# step_up_converter.net
KiCad netlist of a schematic drawn in EAGLE
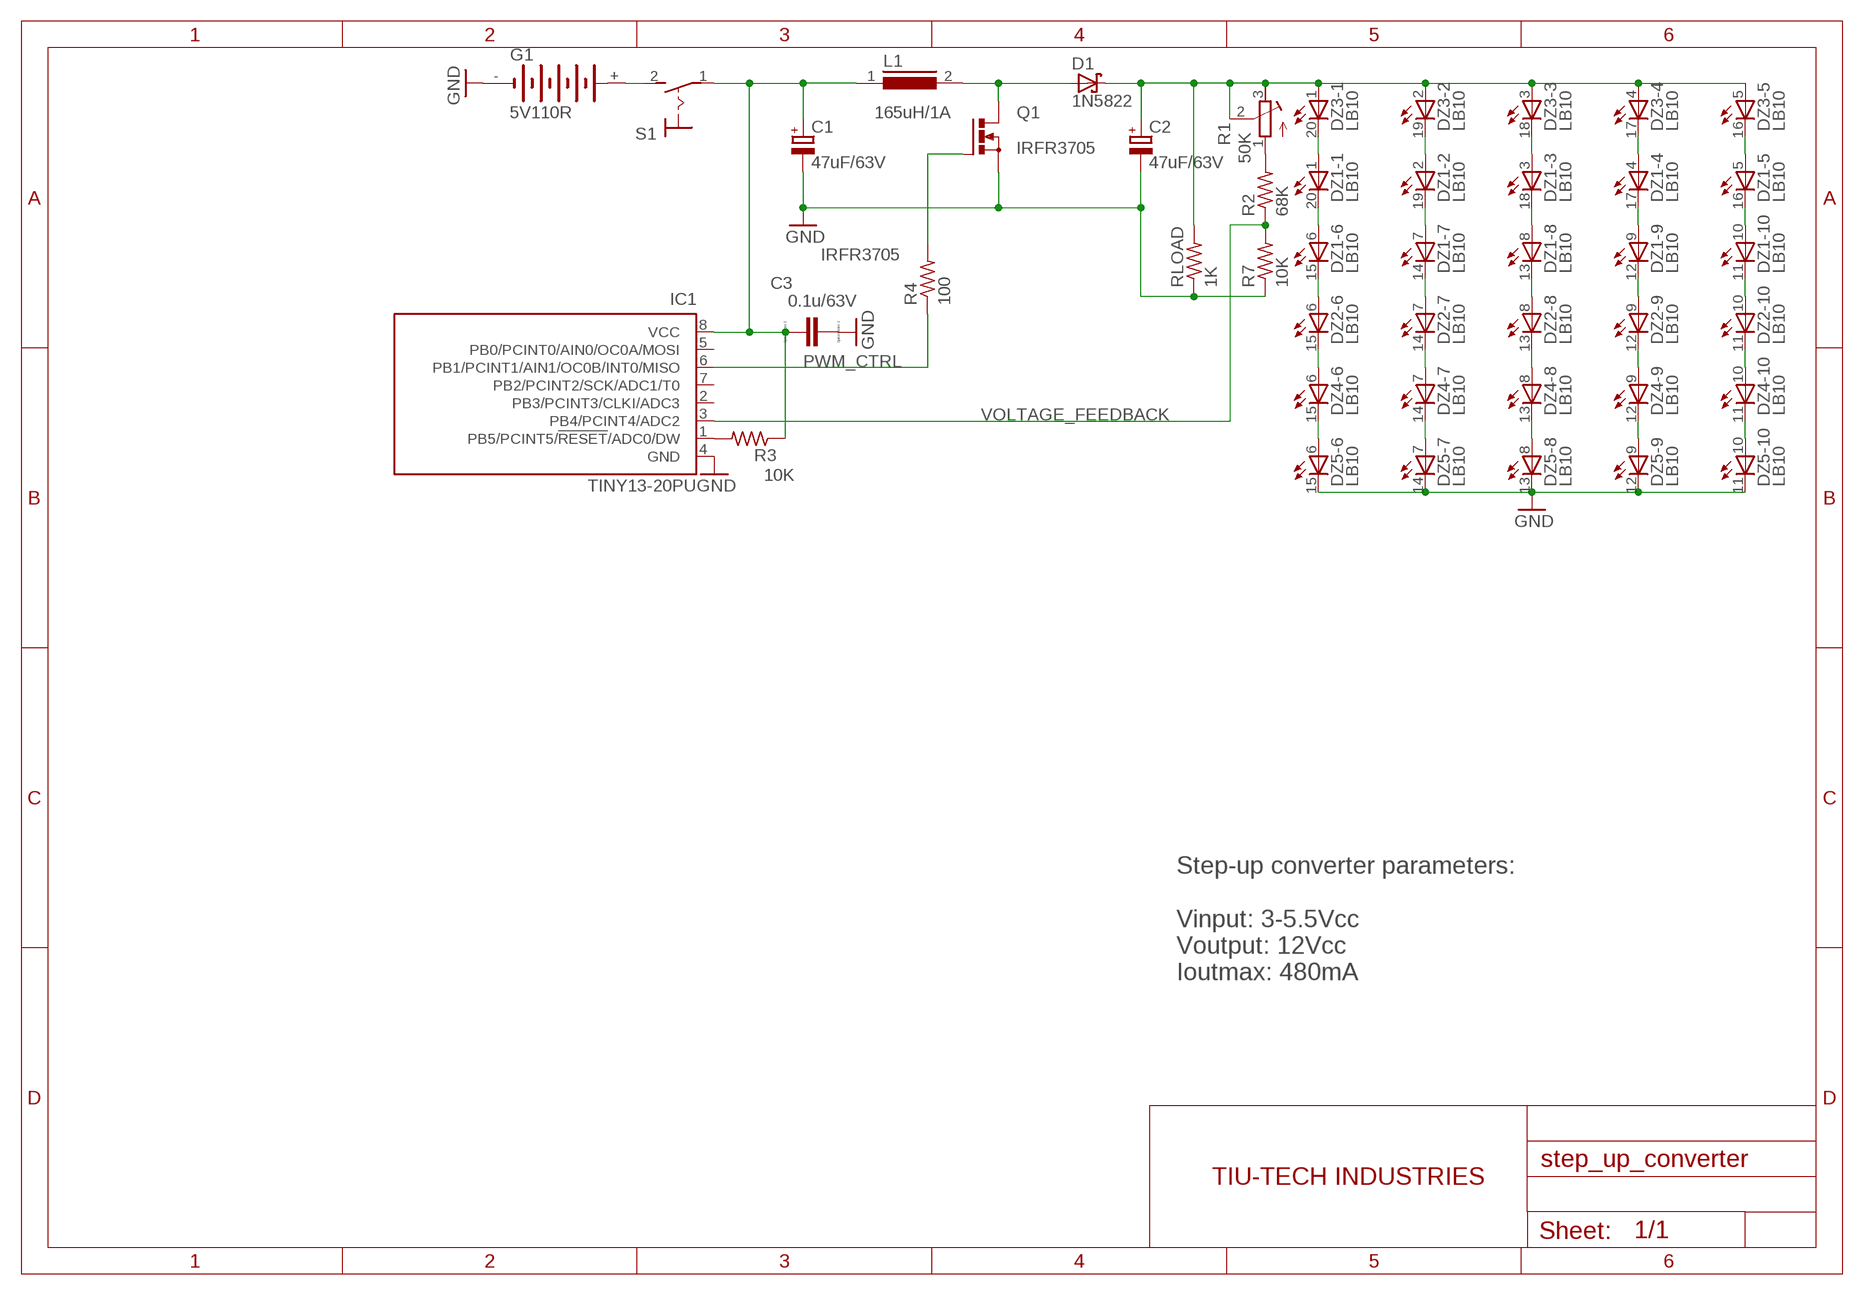
[diagram p0: schematic, sheet 1]

(export (version "E")
  (design (tool "Eeschema 10.0.6"))
  (components
    (comp (ref "C1")
      (value "47uF/63V")
      (footprint "eagle-import:E2,5-6")
      (libsource (lib "eagle-import") (part "CPOL-EUE2.5-6"))
    )
    (comp (ref "C2")
      (value "47uF/63V")
      (footprint "eagle-import:E2,5-6")
      (libsource (lib "eagle-import") (part "CPOL-EUE2.5-6"))
    )
    (comp (ref "C3")
      (value "0.1u/63V")
      (footprint "eagle-import:C025-024X044")
      (libsource (lib "eagle-import") (part "C-EU025-024X044"))
    )
    (comp (ref "D1")
      (value "1N5822")
      (footprint "eagle-import:CB429-17")
      (libsource (lib "eagle-import") (part "SCHOTTKY-DIODECB429-17"))
    )
    (comp (ref "DZ1")
      (value "LB10")
      (footprint "eagle-import:LB10")
      (libsource (lib "eagle-import") (part "LB10"))
    )
    (comp (ref "DZ2")
      (value "LB10")
      (footprint "eagle-import:LB10")
      (libsource (lib "eagle-import") (part "LB10"))
    )
    (comp (ref "DZ3")
      (value "LB10")
      (footprint "eagle-import:LB10")
      (libsource (lib "eagle-import") (part "LB10"))
    )
    (comp (ref "DZ4")
      (value "LB10")
      (footprint "eagle-import:LB10")
      (libsource (lib "eagle-import") (part "LB10"))
    )
    (comp (ref "DZ5")
      (value "LB10")
      (footprint "eagle-import:LB10")
      (libsource (lib "eagle-import") (part "LB10"))
    )
    (comp (ref "G1")
      (value "5V110R")
      (footprint "eagle-import:5V110R")
      (libsource (lib "eagle-import") (part "5V110R"))
    )
    (comp (ref "IC1")
      (value "TINY13-20PU")
      (footprint "eagle-import:DIL08")
      (fields (field (name "MPN") "ATTINY13-20PU"))
      (libsource (lib "eagle-import") (part "TINY13PU-20"))
    )
    (comp (ref "L1")
      (value "82114R")
      (footprint "eagle-import:82114R")
      (libsource (lib "eagle-import") (part "82114R"))
    )
    (comp (ref "R1")
      (value "50K")
      (footprint "eagle-import:RTRIM64P")
      (libsource (lib "eagle-import") (part "R-TRIMM64P"))
    )
    (comp (ref "R2")
      (value "68K")
      (footprint "eagle-import:0204_5")
      (libsource (lib "eagle-import") (part "R-US_0204/5"))
    )
    (comp (ref "R3")
      (value "10K")
      (footprint "eagle-import:0204_5")
      (libsource (lib "eagle-import") (part "R-US_0204/5"))
    )
    (comp (ref "R4")
      (value "100")
      (footprint "eagle-import:0204_5")
      (libsource (lib "eagle-import") (part "R-US_0204/5"))
    )
    (comp (ref "R7")
      (value "10K")
      (footprint "eagle-import:0204_5")
      (libsource (lib "eagle-import") (part "R-US_0204/5"))
    )
    (comp (ref "RLOAD")
      (value "1K")
      (footprint "eagle-import:0204_5")
      (libsource (lib "eagle-import") (part "R-US_0204/5"))
    )
    (comp (ref "S1")
      (value "MS243")
      (footprint "eagle-import:MS243")
      (libsource (lib "eagle-import") (part "MS243"))
    )
  )
  (nets
    (net (code "1") (name "/PWM_CTRL") (class "Default")
      (node (ref "IC1") (pin "6") (pinfunction "PB1/PCINT1/AIN1/OC0B/INT0/MISO_6") (pintype "bidirectional"))
      (node (ref "R4") (pin "1") (pinfunction "1_1") (pintype "passive"))
    )
    (net (code "2") (name "/VOLTAGE_FEEDBACK") (class "Default")
      (node (ref "IC1") (pin "3") (pinfunction "PB4/PCINT4/ADC2_3") (pintype "bidirectional"))
      (node (ref "R2") (pin "1") (pinfunction "1_1") (pintype "passive"))
      (node (ref "R7") (pin "2") (pinfunction "2_2") (pintype "passive"))
    )
    (net (code "3") (name "GND") (class "Default")
      (node (ref "C1") (pin "-") (pinfunction "-_-") (pintype "passive"))
      (node (ref "C2") (pin "-") (pinfunction "-_-") (pintype "passive"))
      (node (ref "C3") (pin "1") (pinfunction "1_1") (pintype "passive"))
      (node (ref "DZ5") (pin "11") (pinfunction "C_11") (pintype "passive"))
      (node (ref "DZ5") (pin "12") (pinfunction "C_12") (pintype "passive"))
      (node (ref "DZ5") (pin "13") (pinfunction "C_13") (pintype "passive"))
      (node (ref "DZ5") (pin "14") (pinfunction "C_14") (pintype "passive"))
      (node (ref "DZ5") (pin "15") (pinfunction "C_15") (pintype "passive"))
      (node (ref "G1") (pin "-") (pinfunction "-_-") (pintype "passive"))
      (node (ref "IC1") (pin "4") (pinfunction "GND_4") (pintype "power_in"))
      (node (ref "R7") (pin "1") (pinfunction "1_1") (pintype "passive"))
      (node (ref "RLOAD") (pin "1") (pinfunction "1_1") (pintype "passive"))
    )
    (net (code "4") (name "Net-(D1-PadA)") (class "Default")
      (node (ref "D1") (pin "A") (pinfunction "A_A") (pintype "passive"))
      (node (ref "L1") (pin "2") (pinfunction "2_2") (pintype "passive"))
    )
    (net (code "5") (name "Net-(DZ1A-A)") (class "Default")
      (node (ref "DZ1") (pin "1") (pinfunction "A_1") (pintype "passive"))
      (node (ref "DZ3") (pin "20") (pinfunction "C_20") (pintype "passive"))
    )
    (net (code "6") (name "Net-(DZ1A-C)") (class "Default")
      (node (ref "DZ1") (pin "20") (pinfunction "C_20") (pintype "passive"))
      (node (ref "DZ1") (pin "6") (pinfunction "A_6") (pintype "passive"))
    )
    (net (code "7") (name "Net-(DZ1B-A)") (class "Default")
      (node (ref "DZ1") (pin "10") (pinfunction "A_10") (pintype "passive"))
      (node (ref "DZ1") (pin "16") (pinfunction "C_16") (pintype "passive"))
    )
    (net (code "8") (name "Net-(DZ1B-C)") (class "Default")
      (node (ref "DZ1") (pin "11") (pinfunction "C_11") (pintype "passive"))
      (node (ref "DZ2") (pin "10") (pinfunction "A_10") (pintype "passive"))
    )
    (net (code "9") (name "Net-(DZ1C-A)") (class "Default")
      (node (ref "DZ1") (pin "2") (pinfunction "A_2") (pintype "passive"))
      (node (ref "DZ3") (pin "19") (pinfunction "C_19") (pintype "passive"))
    )
    (net (code "10") (name "Net-(DZ1C-C)") (class "Default")
      (node (ref "DZ1") (pin "19") (pinfunction "C_19") (pintype "passive"))
      (node (ref "DZ1") (pin "7") (pinfunction "A_7") (pintype "passive"))
    )
    (net (code "11") (name "Net-(DZ1D-A)") (class "Default")
      (node (ref "DZ1") (pin "3") (pinfunction "A_3") (pintype "passive"))
      (node (ref "DZ3") (pin "18") (pinfunction "C_18") (pintype "passive"))
    )
    (net (code "12") (name "Net-(DZ1D-C)") (class "Default")
      (node (ref "DZ1") (pin "18") (pinfunction "C_18") (pintype "passive"))
      (node (ref "DZ1") (pin "8") (pinfunction "A_8") (pintype "passive"))
    )
    (net (code "13") (name "Net-(DZ1E-A)") (class "Default")
      (node (ref "DZ1") (pin "4") (pinfunction "A_4") (pintype "passive"))
      (node (ref "DZ3") (pin "17") (pinfunction "C_17") (pintype "passive"))
    )
    (net (code "14") (name "Net-(DZ1E-C)") (class "Default")
      (node (ref "DZ1") (pin "17") (pinfunction "C_17") (pintype "passive"))
      (node (ref "DZ1") (pin "9") (pinfunction "A_9") (pintype "passive"))
    )
    (net (code "15") (name "Net-(DZ1F-A)") (class "Default")
      (node (ref "DZ1") (pin "5") (pinfunction "A_5") (pintype "passive"))
      (node (ref "DZ3") (pin "16") (pinfunction "C_16") (pintype "passive"))
    )
    (net (code "16") (name "Net-(DZ1G-C)") (class "Default")
      (node (ref "DZ1") (pin "15") (pinfunction "C_15") (pintype "passive"))
      (node (ref "DZ2") (pin "6") (pinfunction "A_6") (pintype "passive"))
    )
    (net (code "17") (name "Net-(DZ1H-C)") (class "Default")
      (node (ref "DZ1") (pin "14") (pinfunction "C_14") (pintype "passive"))
      (node (ref "DZ2") (pin "7") (pinfunction "A_7") (pintype "passive"))
    )
    (net (code "18") (name "Net-(DZ1I-C)") (class "Default")
      (node (ref "DZ1") (pin "13") (pinfunction "C_13") (pintype "passive"))
      (node (ref "DZ2") (pin "8") (pinfunction "A_8") (pintype "passive"))
    )
    (net (code "19") (name "Net-(DZ1J-C)") (class "Default")
      (node (ref "DZ1") (pin "12") (pinfunction "C_12") (pintype "passive"))
      (node (ref "DZ2") (pin "9") (pinfunction "A_9") (pintype "passive"))
    )
    (net (code "20") (name "Net-(DZ2B-C)") (class "Default")
      (node (ref "DZ2") (pin "11") (pinfunction "C_11") (pintype "passive"))
      (node (ref "DZ4") (pin "10") (pinfunction "A_10") (pintype "passive"))
    )
    (net (code "21") (name "Net-(DZ2G-C)") (class "Default")
      (node (ref "DZ2") (pin "15") (pinfunction "C_15") (pintype "passive"))
      (node (ref "DZ4") (pin "6") (pinfunction "A_6") (pintype "passive"))
    )
    (net (code "22") (name "Net-(DZ2H-C)") (class "Default")
      (node (ref "DZ2") (pin "14") (pinfunction "C_14") (pintype "passive"))
      (node (ref "DZ4") (pin "7") (pinfunction "A_7") (pintype "passive"))
    )
    (net (code "23") (name "Net-(DZ2I-C)") (class "Default")
      (node (ref "DZ2") (pin "13") (pinfunction "C_13") (pintype "passive"))
      (node (ref "DZ4") (pin "8") (pinfunction "A_8") (pintype "passive"))
    )
    (net (code "24") (name "Net-(DZ2J-C)") (class "Default")
      (node (ref "DZ2") (pin "12") (pinfunction "C_12") (pintype "passive"))
      (node (ref "DZ4") (pin "9") (pinfunction "A_9") (pintype "passive"))
    )
    (net (code "25") (name "Net-(DZ3A-A)") (class "Default")
      (node (ref "C2") (pin "+") (pinfunction "+_+") (pintype "passive"))
      (node (ref "D1") (pin "C") (pinfunction "C_C") (pintype "passive"))
      (node (ref "DZ3") (pin "1") (pinfunction "A_1") (pintype "passive"))
      (node (ref "DZ3") (pin "2") (pinfunction "A_2") (pintype "passive"))
      (node (ref "DZ3") (pin "3") (pinfunction "A_3") (pintype "passive"))
      (node (ref "DZ3") (pin "4") (pinfunction "A_4") (pintype "passive"))
      (node (ref "DZ3") (pin "5") (pinfunction "A_5") (pintype "passive"))
      (node (ref "R1") (pin "2") (pinfunction "S_2") (pintype "passive"))
      (node (ref "R1") (pin "3") (pinfunction "A_3") (pintype "passive"))
      (node (ref "RLOAD") (pin "2") (pinfunction "2_2") (pintype "passive"))
    )
    (net (code "26") (name "Net-(DZ4B-C)") (class "Default")
      (node (ref "DZ4") (pin "11") (pinfunction "C_11") (pintype "passive"))
      (node (ref "DZ5") (pin "10") (pinfunction "A_10") (pintype "passive"))
    )
    (net (code "27") (name "Net-(DZ4G-C)") (class "Default")
      (node (ref "DZ4") (pin "15") (pinfunction "C_15") (pintype "passive"))
      (node (ref "DZ5") (pin "6") (pinfunction "A_6") (pintype "passive"))
    )
    (net (code "28") (name "Net-(DZ4H-C)") (class "Default")
      (node (ref "DZ4") (pin "14") (pinfunction "C_14") (pintype "passive"))
      (node (ref "DZ5") (pin "7") (pinfunction "A_7") (pintype "passive"))
    )
    (net (code "29") (name "Net-(DZ4I-C)") (class "Default")
      (node (ref "DZ4") (pin "13") (pinfunction "C_13") (pintype "passive"))
      (node (ref "DZ5") (pin "8") (pinfunction "A_8") (pintype "passive"))
    )
    (net (code "30") (name "Net-(DZ4J-C)") (class "Default")
      (node (ref "DZ4") (pin "12") (pinfunction "C_12") (pintype "passive"))
      (node (ref "DZ5") (pin "9") (pinfunction "A_9") (pintype "passive"))
    )
    (net (code "31") (name "Net-(IC1-PB5{slash}PCINT5{slash}~{RESET}{slash}ADC0{slash}DW)") (class "Default")
      (node (ref "IC1") (pin "1") (pinfunction "PB5/PCINT5/~{RESET}/ADC0/DW_1") (pintype "bidirectional"))
      (node (ref "R3") (pin "2") (pinfunction "2_2") (pintype "passive"))
    )
    (net (code "32") (name "Net-(IC1-VCC)") (class "Default")
      (node (ref "C1") (pin "+") (pinfunction "+_+") (pintype "passive"))
      (node (ref "C3") (pin "2") (pinfunction "2_2") (pintype "passive"))
      (node (ref "IC1") (pin "8") (pinfunction "VCC_8") (pintype "power_in"))
      (node (ref "L1") (pin "1") (pinfunction "1_1") (pintype "passive"))
      (node (ref "R3") (pin "1") (pinfunction "1_1") (pintype "passive"))
      (node (ref "S1") (pin "1") (pinfunction "P_1") (pintype "passive"))
    )
    (net (code "33") (name "Net-(R1-E)") (class "Default")
      (node (ref "R1") (pin "1") (pinfunction "E_1") (pintype "passive"))
      (node (ref "R2") (pin "2") (pinfunction "2_2") (pintype "passive"))
    )
    (net (code "34") (name "Net-(S1-S)") (class "Default")
      (node (ref "G1") (pin "+") (pinfunction "+_+") (pintype "passive"))
      (node (ref "S1") (pin "2") (pinfunction "S_2") (pintype "passive"))
    )
    (net (code "35") (name "unconnected-(G1-+-Pad+@1)") (class "Default")
      (node (ref "G1") (pin "+@1") (pinfunction "+_+@1") (pintype "passive"))
    )
    (net (code "36") (name "unconnected-(IC1-PB0{slash}PCINT0{slash}AIN0{slash}OC0A{slash}MOSI-Pad5)") (class "Default")
      (node (ref "IC1") (pin "5") (pinfunction "PB0/PCINT0/AIN0/OC0A/MOSI_5") (pintype "bidirectional"))
    )
    (net (code "37") (name "unconnected-(IC1-PB2{slash}PCINT2{slash}SCK{slash}ADC1{slash}T0-Pad7)") (class "Default")
      (node (ref "IC1") (pin "7") (pinfunction "PB2/PCINT2/SCK/ADC1/T0_7") (pintype "bidirectional"))
    )
    (net (code "38") (name "unconnected-(IC1-PB3{slash}PCINT3{slash}CLKI{slash}ADC3-Pad2)") (class "Default")
      (node (ref "IC1") (pin "2") (pinfunction "PB3/PCINT3/CLKI/ADC3_2") (pintype "bidirectional"))
    )
    (net (code "39") (name "unconnected-(R4-Pad2)") (class "Default")
      (node (ref "R4") (pin "2") (pinfunction "2_2") (pintype "passive"))
    )
  )
)
